# HVAC8-2.net
KiCad netlist of a schematic drawn in EAGLE
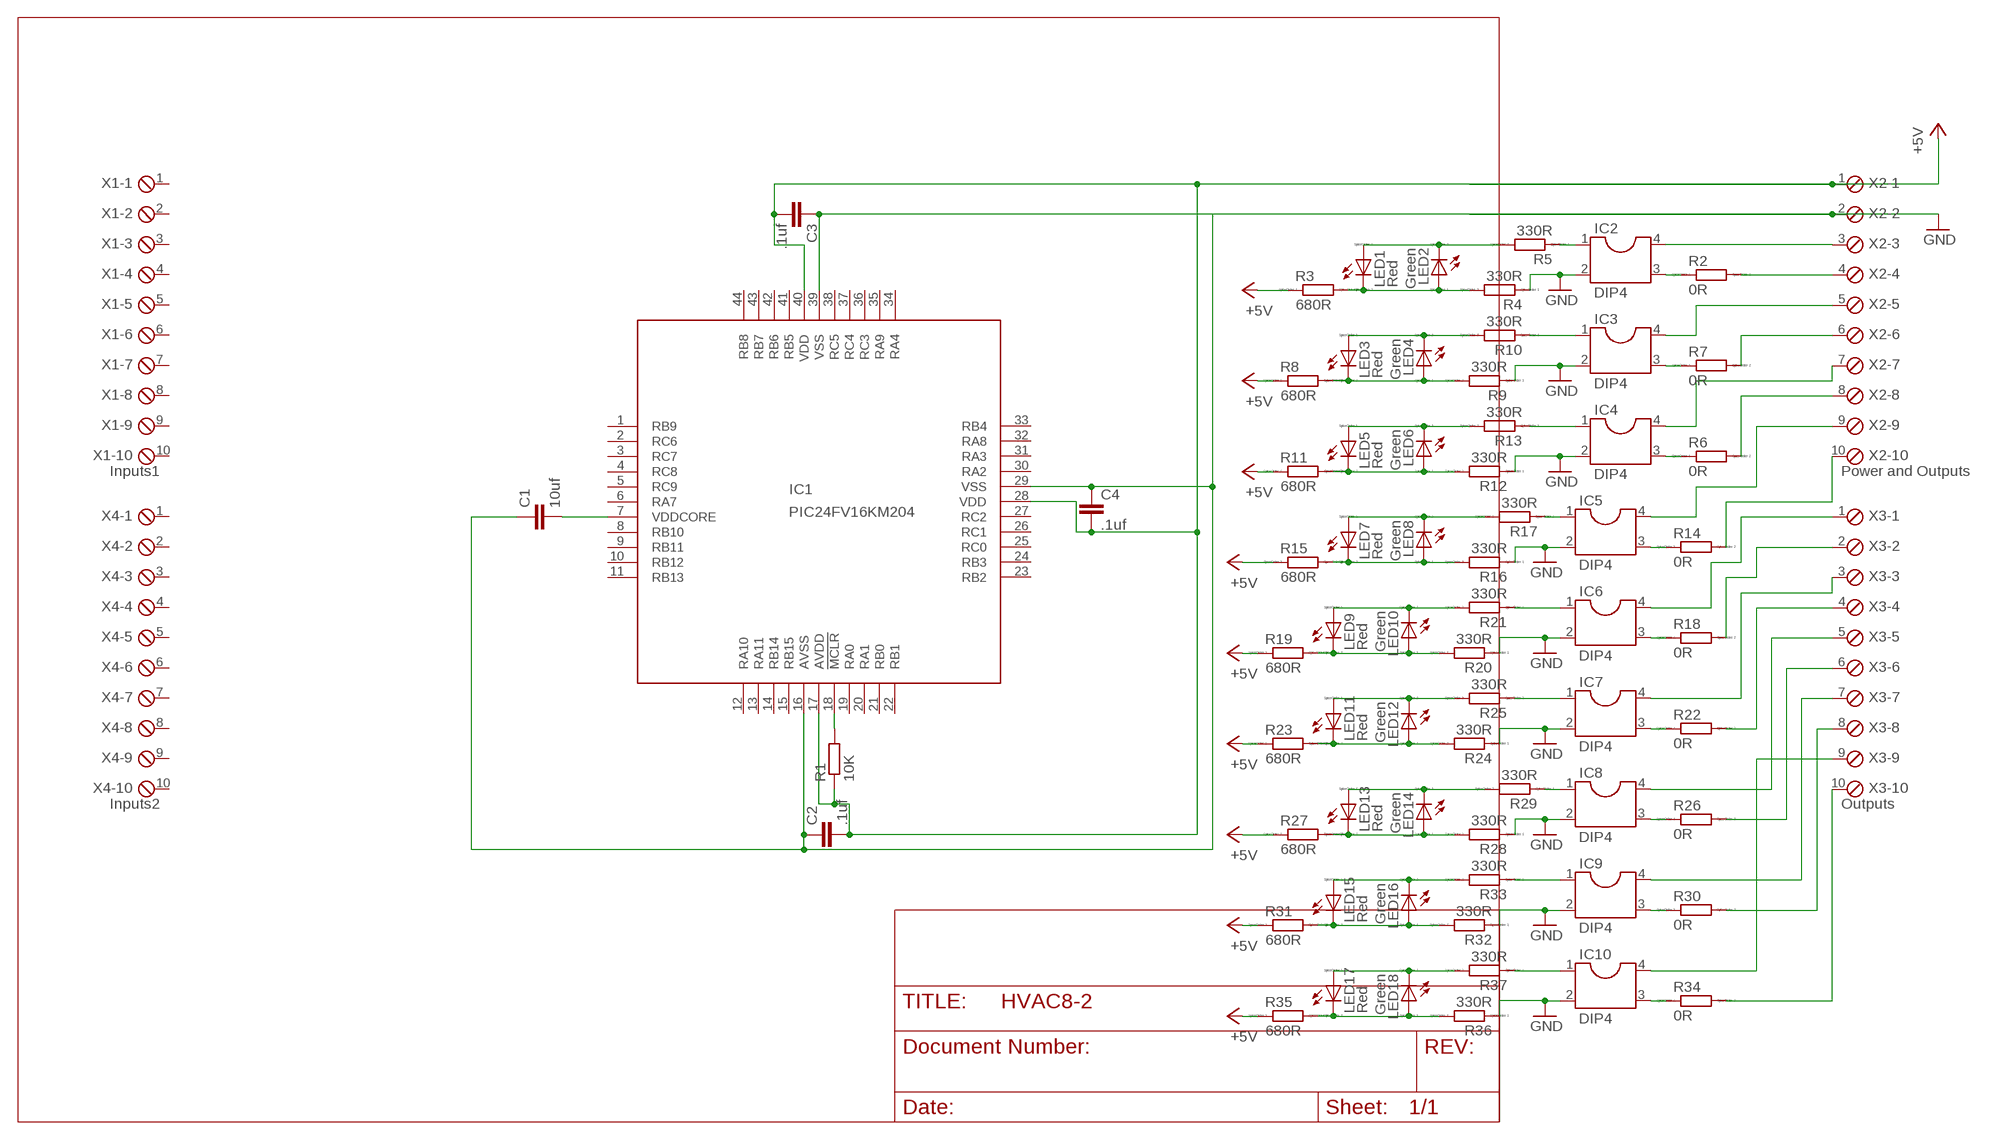
[diagram p0: schematic, sheet 1]

(export (version "E")
  (design (tool "Eeschema 10.0.6"))
  (components
    (comp (ref "C1")
      (value "10uf")
      (footprint "eagle-import:C1206")
      (libsource (lib "eagle-import") (part "C-EUC1206"))
    )
    (comp (ref "C2")
      (value ".1uf")
      (footprint "eagle-import:C1206")
      (libsource (lib "eagle-import") (part "C-EUC1206"))
    )
    (comp (ref "C3")
      (value ".1uf")
      (footprint "eagle-import:C1206")
      (libsource (lib "eagle-import") (part "C-EUC1206"))
    )
    (comp (ref "C4")
      (value ".1uf")
      (footprint "eagle-import:C1206")
      (libsource (lib "eagle-import") (part "C-EUC1206"))
    )
    (comp (ref "IC1")
      (value "PIC24FV16KM204")
      (footprint "eagle-import:TQFP44")
      (libsource (lib "eagle-import") (part "PIC24FV16KM204"))
    )
    (comp (ref "IC2")
      (value "DIP4")
      (footprint "eagle-import:SOCKET-04")
      (libsource (lib "eagle-import") (part "DIL4S"))
    )
    (comp (ref "IC3")
      (value "DIP4")
      (footprint "eagle-import:SOCKET-04")
      (libsource (lib "eagle-import") (part "DIL4S"))
    )
    (comp (ref "IC4")
      (value "DIP4")
      (footprint "eagle-import:SOCKET-04")
      (libsource (lib "eagle-import") (part "DIL4S"))
    )
    (comp (ref "IC5")
      (value "DIP4")
      (footprint "eagle-import:SOCKET-04")
      (libsource (lib "eagle-import") (part "DIL4S"))
    )
    (comp (ref "IC6")
      (value "DIP4")
      (footprint "eagle-import:SOCKET-04")
      (libsource (lib "eagle-import") (part "DIL4S"))
    )
    (comp (ref "IC7")
      (value "DIP4")
      (footprint "eagle-import:SOCKET-04")
      (libsource (lib "eagle-import") (part "DIL4S"))
    )
    (comp (ref "IC8")
      (value "DIP4")
      (footprint "eagle-import:SOCKET-04")
      (libsource (lib "eagle-import") (part "DIL4S"))
    )
    (comp (ref "IC9")
      (value "DIP4")
      (footprint "eagle-import:SOCKET-04")
      (libsource (lib "eagle-import") (part "DIL4S"))
    )
    (comp (ref "IC10")
      (value "DIP4")
      (footprint "eagle-import:SOCKET-04")
      (libsource (lib "eagle-import") (part "DIL4S"))
    )
    (comp (ref "LED1")
      (value "Red")
      (footprint "eagle-import:LED_1206")
      (libsource (lib "eagle-import") (part "LED_E"))
    )
    (comp (ref "LED2")
      (value "Green")
      (footprint "eagle-import:LED_1206")
      (libsource (lib "eagle-import") (part "LED_E"))
    )
    (comp (ref "LED3")
      (value "Red")
      (footprint "eagle-import:LED_1206")
      (libsource (lib "eagle-import") (part "LED_E"))
    )
    (comp (ref "LED4")
      (value "Green")
      (footprint "eagle-import:LED_1206")
      (libsource (lib "eagle-import") (part "LED_E"))
    )
    (comp (ref "LED5")
      (value "Red")
      (footprint "eagle-import:LED_1206")
      (libsource (lib "eagle-import") (part "LED_E"))
    )
    (comp (ref "LED6")
      (value "Green")
      (footprint "eagle-import:LED_1206")
      (libsource (lib "eagle-import") (part "LED_E"))
    )
    (comp (ref "LED7")
      (value "Red")
      (footprint "eagle-import:LED_1206")
      (libsource (lib "eagle-import") (part "LED_E"))
    )
    (comp (ref "LED8")
      (value "Green")
      (footprint "eagle-import:LED_1206")
      (libsource (lib "eagle-import") (part "LED_E"))
    )
    (comp (ref "LED9")
      (value "Red")
      (footprint "eagle-import:LED_1206")
      (libsource (lib "eagle-import") (part "LED_E"))
    )
    (comp (ref "LED10")
      (value "Green")
      (footprint "eagle-import:LED_1206")
      (libsource (lib "eagle-import") (part "LED_E"))
    )
    (comp (ref "LED11")
      (value "Red")
      (footprint "eagle-import:LED_1206")
      (libsource (lib "eagle-import") (part "LED_E"))
    )
    (comp (ref "LED12")
      (value "Green")
      (footprint "eagle-import:LED_1206")
      (libsource (lib "eagle-import") (part "LED_E"))
    )
    (comp (ref "LED13")
      (value "Red")
      (footprint "eagle-import:LED_1206")
      (libsource (lib "eagle-import") (part "LED_E"))
    )
    (comp (ref "LED14")
      (value "Green")
      (footprint "eagle-import:LED_1206")
      (libsource (lib "eagle-import") (part "LED_E"))
    )
    (comp (ref "LED15")
      (value "Red")
      (footprint "eagle-import:LED_1206")
      (libsource (lib "eagle-import") (part "LED_E"))
    )
    (comp (ref "LED16")
      (value "Green")
      (footprint "eagle-import:LED_1206")
      (libsource (lib "eagle-import") (part "LED_E"))
    )
    (comp (ref "LED17")
      (value "Red")
      (footprint "eagle-import:LED_1206")
      (libsource (lib "eagle-import") (part "LED_E"))
    )
    (comp (ref "LED18")
      (value "Green")
      (footprint "eagle-import:LED_1206")
      (libsource (lib "eagle-import") (part "LED_E"))
    )
    (comp (ref "R1")
      (value "10K")
      (footprint "eagle-import:R1206")
      (libsource (lib "eagle-import") (part "R-EU_R1206"))
    )
    (comp (ref "R2")
      (value "0R")
      (footprint "eagle-import:R1206")
      (libsource (lib "eagle-import") (part "RR1206"))
    )
    (comp (ref "R3")
      (value "680R")
      (footprint "eagle-import:R1206")
      (libsource (lib "eagle-import") (part "RR1206"))
    )
    (comp (ref "R4")
      (value "330R")
      (footprint "eagle-import:R1206")
      (libsource (lib "eagle-import") (part "RR1206"))
    )
    (comp (ref "R5")
      (value "330R")
      (footprint "eagle-import:R1206")
      (libsource (lib "eagle-import") (part "RR1206"))
    )
    (comp (ref "R6")
      (value "0R")
      (footprint "eagle-import:R1206")
      (libsource (lib "eagle-import") (part "RR1206"))
    )
    (comp (ref "R7")
      (value "0R")
      (footprint "eagle-import:R1206")
      (libsource (lib "eagle-import") (part "RR1206"))
    )
    (comp (ref "R8")
      (value "680R")
      (footprint "eagle-import:R1206")
      (libsource (lib "eagle-import") (part "RR1206"))
    )
    (comp (ref "R9")
      (value "330R")
      (footprint "eagle-import:R1206")
      (libsource (lib "eagle-import") (part "RR1206"))
    )
    (comp (ref "R10")
      (value "330R")
      (footprint "eagle-import:R1206")
      (libsource (lib "eagle-import") (part "RR1206"))
    )
    (comp (ref "R11")
      (value "680R")
      (footprint "eagle-import:R1206")
      (libsource (lib "eagle-import") (part "RR1206"))
    )
    (comp (ref "R12")
      (value "330R")
      (footprint "eagle-import:R1206")
      (libsource (lib "eagle-import") (part "RR1206"))
    )
    (comp (ref "R13")
      (value "330R")
      (footprint "eagle-import:R1206")
      (libsource (lib "eagle-import") (part "RR1206"))
    )
    (comp (ref "R14")
      (value "0R")
      (footprint "eagle-import:R1206")
      (libsource (lib "eagle-import") (part "RR1206"))
    )
    (comp (ref "R15")
      (value "680R")
      (footprint "eagle-import:R1206")
      (libsource (lib "eagle-import") (part "RR1206"))
    )
    (comp (ref "R16")
      (value "330R")
      (footprint "eagle-import:R1206")
      (libsource (lib "eagle-import") (part "RR1206"))
    )
    (comp (ref "R17")
      (value "330R")
      (footprint "eagle-import:R1206")
      (libsource (lib "eagle-import") (part "RR1206"))
    )
    (comp (ref "R18")
      (value "0R")
      (footprint "eagle-import:R1206")
      (libsource (lib "eagle-import") (part "RR1206"))
    )
    (comp (ref "R19")
      (value "680R")
      (footprint "eagle-import:R1206")
      (libsource (lib "eagle-import") (part "RR1206"))
    )
    (comp (ref "R20")
      (value "330R")
      (footprint "eagle-import:R1206")
      (libsource (lib "eagle-import") (part "RR1206"))
    )
    (comp (ref "R21")
      (value "330R")
      (footprint "eagle-import:R1206")
      (libsource (lib "eagle-import") (part "RR1206"))
    )
    (comp (ref "R22")
      (value "0R")
      (footprint "eagle-import:R1206")
      (libsource (lib "eagle-import") (part "RR1206"))
    )
    (comp (ref "R23")
      (value "680R")
      (footprint "eagle-import:R1206")
      (libsource (lib "eagle-import") (part "RR1206"))
    )
    (comp (ref "R24")
      (value "330R")
      (footprint "eagle-import:R1206")
      (libsource (lib "eagle-import") (part "RR1206"))
    )
    (comp (ref "R25")
      (value "330R")
      (footprint "eagle-import:R1206")
      (libsource (lib "eagle-import") (part "RR1206"))
    )
    (comp (ref "R26")
      (value "0R")
      (footprint "eagle-import:R1206")
      (libsource (lib "eagle-import") (part "RR1206"))
    )
    (comp (ref "R27")
      (value "680R")
      (footprint "eagle-import:R1206")
      (libsource (lib "eagle-import") (part "RR1206"))
    )
    (comp (ref "R28")
      (value "330R")
      (footprint "eagle-import:R1206")
      (libsource (lib "eagle-import") (part "RR1206"))
    )
    (comp (ref "R29")
      (value "330R")
      (footprint "eagle-import:R1206")
      (libsource (lib "eagle-import") (part "RR1206"))
    )
    (comp (ref "R30")
      (value "0R")
      (footprint "eagle-import:R1206")
      (libsource (lib "eagle-import") (part "RR1206"))
    )
    (comp (ref "R31")
      (value "680R")
      (footprint "eagle-import:R1206")
      (libsource (lib "eagle-import") (part "RR1206"))
    )
    (comp (ref "R32")
      (value "330R")
      (footprint "eagle-import:R1206")
      (libsource (lib "eagle-import") (part "RR1206"))
    )
    (comp (ref "R33")
      (value "330R")
      (footprint "eagle-import:R1206")
      (libsource (lib "eagle-import") (part "RR1206"))
    )
    (comp (ref "R34")
      (value "0R")
      (footprint "eagle-import:R1206")
      (libsource (lib "eagle-import") (part "RR1206"))
    )
    (comp (ref "R35")
      (value "680R")
      (footprint "eagle-import:R1206")
      (libsource (lib "eagle-import") (part "RR1206"))
    )
    (comp (ref "R36")
      (value "330R")
      (footprint "eagle-import:R1206")
      (libsource (lib "eagle-import") (part "RR1206"))
    )
    (comp (ref "R37")
      (value "330R")
      (footprint "eagle-import:R1206")
      (libsource (lib "eagle-import") (part "RR1206"))
    )
    (comp (ref "X1")
      (value "Inputs1")
      (footprint "eagle-import:10POL254")
      (libsource (lib "eagle-import") (part "MPT10"))
    )
    (comp (ref "X2")
      (value "Power and Outputs")
      (footprint "eagle-import:10POL254")
      (libsource (lib "eagle-import") (part "MPT10"))
    )
    (comp (ref "X3")
      (value "Outputs")
      (footprint "eagle-import:10POL254")
      (libsource (lib "eagle-import") (part "MPT10"))
    )
    (comp (ref "X4")
      (value "Inputs2")
      (footprint "eagle-import:10POL254")
      (libsource (lib "eagle-import") (part "MPT10"))
    )
  )
  (nets
    (net (code "1") (name "+5V") (class "Default")
      (node (ref "C2") (pin "2") (pinfunction "2_2") (pintype "passive"))
      (node (ref "C3") (pin "2") (pinfunction "2_2") (pintype "passive"))
      (node (ref "C4") (pin "2") (pinfunction "2_2") (pintype "passive"))
      (node (ref "IC1") (pin "17") (pinfunction "AVDD_17") (pintype "power_in"))
      (node (ref "IC1") (pin "28") (pinfunction "VDD_28") (pintype "power_in"))
      (node (ref "IC1") (pin "40") (pinfunction "VDD_40") (pintype "power_in"))
      (node (ref "R1") (pin "1") (pinfunction "1_1") (pintype "passive"))
      (node (ref "R11") (pin "1") (pinfunction "1_1") (pintype "passive"))
      (node (ref "R15") (pin "1") (pinfunction "1_1") (pintype "passive"))
      (node (ref "R19") (pin "1") (pinfunction "1_1") (pintype "passive"))
      (node (ref "R23") (pin "1") (pinfunction "1_1") (pintype "passive"))
      (node (ref "R27") (pin "1") (pinfunction "1_1") (pintype "passive"))
      (node (ref "R3") (pin "1") (pinfunction "1_1") (pintype "passive"))
      (node (ref "R31") (pin "1") (pinfunction "1_1") (pintype "passive"))
      (node (ref "R35") (pin "1") (pinfunction "1_1") (pintype "passive"))
      (node (ref "R8") (pin "1") (pinfunction "1_1") (pintype "passive"))
      (node (ref "X2") (pin "1") (pinfunction "1_1") (pintype "passive"))
    )
    (net (code "2") (name "GND") (class "Default")
      (node (ref "C1") (pin "1") (pinfunction "1_1") (pintype "passive"))
      (node (ref "C2") (pin "1") (pinfunction "1_1") (pintype "passive"))
      (node (ref "C3") (pin "1") (pinfunction "1_1") (pintype "passive"))
      (node (ref "C4") (pin "1") (pinfunction "1_1") (pintype "passive"))
      (node (ref "IC1") (pin "16") (pinfunction "AVSS_16") (pintype "power_in"))
      (node (ref "IC1") (pin "29") (pinfunction "VSS_29") (pintype "power_in"))
      (node (ref "IC1") (pin "39") (pinfunction "VSS_39") (pintype "power_in"))
      (node (ref "IC10") (pin "2") (pinfunction "2_2") (pintype "passive"))
      (node (ref "IC2") (pin "2") (pinfunction "2_2") (pintype "passive"))
      (node (ref "IC3") (pin "2") (pinfunction "2_2") (pintype "passive"))
      (node (ref "IC4") (pin "2") (pinfunction "2_2") (pintype "passive"))
      (node (ref "IC5") (pin "2") (pinfunction "2_2") (pintype "passive"))
      (node (ref "IC6") (pin "2") (pinfunction "2_2") (pintype "passive"))
      (node (ref "IC7") (pin "2") (pinfunction "2_2") (pintype "passive"))
      (node (ref "IC8") (pin "2") (pinfunction "2_2") (pintype "passive"))
      (node (ref "IC9") (pin "2") (pinfunction "2_2") (pintype "passive"))
      (node (ref "R12") (pin "1") (pinfunction "1_1") (pintype "passive"))
      (node (ref "R16") (pin "1") (pinfunction "1_1") (pintype "passive"))
      (node (ref "R20") (pin "1") (pinfunction "1_1") (pintype "passive"))
      (node (ref "R24") (pin "1") (pinfunction "1_1") (pintype "passive"))
      (node (ref "R28") (pin "1") (pinfunction "1_1") (pintype "passive"))
      (node (ref "R32") (pin "1") (pinfunction "1_1") (pintype "passive"))
      (node (ref "R36") (pin "1") (pinfunction "1_1") (pintype "passive"))
      (node (ref "R4") (pin "1") (pinfunction "1_1") (pintype "passive"))
      (node (ref "R9") (pin "1") (pinfunction "1_1") (pintype "passive"))
      (node (ref "X2") (pin "2") (pinfunction "1_2") (pintype "passive"))
    )
    (net (code "3") (name "Net-(IC1-VDDCORE)") (class "Default")
      (node (ref "C1") (pin "2") (pinfunction "2_2") (pintype "passive"))
      (node (ref "IC1") (pin "7") (pinfunction "VDDCORE_7") (pintype "power_in"))
    )
    (net (code "4") (name "Net-(IC1-~{MCLR})") (class "Default")
      (node (ref "IC1") (pin "18") (pinfunction "~{MCLR}_18") (pintype "bidirectional"))
      (node (ref "R1") (pin "2") (pinfunction "2_2") (pintype "passive"))
    )
    (net (code "5") (name "Net-(IC2-Pad1)") (class "Default")
      (node (ref "IC2") (pin "1") (pinfunction "1_1") (pintype "passive"))
      (node (ref "R5") (pin "1") (pinfunction "1_1") (pintype "passive"))
    )
    (net (code "6") (name "Net-(IC2-Pad3)") (class "Default")
      (node (ref "IC2") (pin "3") (pinfunction "3_3") (pintype "passive"))
      (node (ref "R2") (pin "1") (pinfunction "1_1") (pintype "passive"))
    )
    (net (code "7") (name "Net-(IC3-Pad1)") (class "Default")
      (node (ref "IC3") (pin "1") (pinfunction "1_1") (pintype "passive"))
      (node (ref "R10") (pin "1") (pinfunction "1_1") (pintype "passive"))
    )
    (net (code "8") (name "Net-(IC3-Pad3)") (class "Default")
      (node (ref "IC3") (pin "3") (pinfunction "3_3") (pintype "passive"))
      (node (ref "R7") (pin "1") (pinfunction "1_1") (pintype "passive"))
    )
    (net (code "9") (name "Net-(IC4-Pad1)") (class "Default")
      (node (ref "IC4") (pin "1") (pinfunction "1_1") (pintype "passive"))
      (node (ref "R13") (pin "1") (pinfunction "1_1") (pintype "passive"))
    )
    (net (code "10") (name "Net-(IC4-Pad3)") (class "Default")
      (node (ref "IC4") (pin "3") (pinfunction "3_3") (pintype "passive"))
      (node (ref "R6") (pin "1") (pinfunction "1_1") (pintype "passive"))
    )
    (net (code "11") (name "Net-(IC5-Pad1)") (class "Default")
      (node (ref "IC5") (pin "1") (pinfunction "1_1") (pintype "passive"))
      (node (ref "R17") (pin "1") (pinfunction "1_1") (pintype "passive"))
    )
    (net (code "12") (name "Net-(IC5-Pad3)") (class "Default")
      (node (ref "IC5") (pin "3") (pinfunction "3_3") (pintype "passive"))
      (node (ref "R14") (pin "1") (pinfunction "1_1") (pintype "passive"))
    )
    (net (code "13") (name "Net-(IC6-Pad1)") (class "Default")
      (node (ref "IC6") (pin "1") (pinfunction "1_1") (pintype "passive"))
      (node (ref "R21") (pin "1") (pinfunction "1_1") (pintype "passive"))
    )
    (net (code "14") (name "Net-(IC6-Pad3)") (class "Default")
      (node (ref "IC6") (pin "3") (pinfunction "3_3") (pintype "passive"))
      (node (ref "R18") (pin "1") (pinfunction "1_1") (pintype "passive"))
    )
    (net (code "15") (name "Net-(IC6-Pad4)") (class "Default")
      (node (ref "IC6") (pin "4") (pinfunction "4_4") (pintype "passive"))
      (node (ref "X3") (pin "1") (pinfunction "1_1") (pintype "passive"))
    )
    (net (code "16") (name "Net-(IC7-Pad1)") (class "Default")
      (node (ref "IC7") (pin "1") (pinfunction "1_1") (pintype "passive"))
      (node (ref "R25") (pin "1") (pinfunction "1_1") (pintype "passive"))
    )
    (net (code "17") (name "Net-(IC7-Pad3)") (class "Default")
      (node (ref "IC7") (pin "3") (pinfunction "3_3") (pintype "passive"))
      (node (ref "R22") (pin "1") (pinfunction "1_1") (pintype "passive"))
    )
    (net (code "18") (name "Net-(IC8-Pad1)") (class "Default")
      (node (ref "IC8") (pin "1") (pinfunction "1_1") (pintype "passive"))
      (node (ref "R29") (pin "1") (pinfunction "1_1") (pintype "passive"))
    )
    (net (code "19") (name "Net-(IC8-Pad3)") (class "Default")
      (node (ref "IC8") (pin "3") (pinfunction "3_3") (pintype "passive"))
      (node (ref "R26") (pin "1") (pinfunction "1_1") (pintype "passive"))
    )
    (net (code "20") (name "Net-(IC9-Pad1)") (class "Default")
      (node (ref "IC9") (pin "1") (pinfunction "1_1") (pintype "passive"))
      (node (ref "R33") (pin "1") (pinfunction "1_1") (pintype "passive"))
    )
    (net (code "21") (name "Net-(IC9-Pad3)") (class "Default")
      (node (ref "IC9") (pin "3") (pinfunction "3_3") (pintype "passive"))
      (node (ref "R30") (pin "1") (pinfunction "1_1") (pintype "passive"))
    )
    (net (code "22") (name "Net-(IC10-Pad1)") (class "Default")
      (node (ref "IC10") (pin "1") (pinfunction "1_1") (pintype "passive"))
      (node (ref "R37") (pin "1") (pinfunction "1_1") (pintype "passive"))
    )
    (net (code "23") (name "Net-(IC10-Pad3)") (class "Default")
      (node (ref "IC10") (pin "3") (pinfunction "3_3") (pintype "passive"))
      (node (ref "R34") (pin "1") (pinfunction "1_1") (pintype "passive"))
    )
    (net (code "24") (name "Net-(LED1-PadA)") (class "Default")
      (node (ref "LED1") (pin "A") (pinfunction "A_A") (pintype "passive"))
      (node (ref "LED2") (pin "C") (pinfunction "C_C") (pintype "passive"))
      (node (ref "R5") (pin "2") (pinfunction "2_2") (pintype "passive"))
    )
    (net (code "25") (name "Net-(LED1-PadC)") (class "Default")
      (node (ref "LED1") (pin "C") (pinfunction "C_C") (pintype "passive"))
      (node (ref "LED2") (pin "A") (pinfunction "A_A") (pintype "passive"))
      (node (ref "R3") (pin "2") (pinfunction "2_2") (pintype "passive"))
      (node (ref "R4") (pin "2") (pinfunction "2_2") (pintype "passive"))
    )
    (net (code "26") (name "Net-(LED3-PadA)") (class "Default")
      (node (ref "LED3") (pin "A") (pinfunction "A_A") (pintype "passive"))
      (node (ref "LED4") (pin "C") (pinfunction "C_C") (pintype "passive"))
      (node (ref "R10") (pin "2") (pinfunction "2_2") (pintype "passive"))
    )
    (net (code "27") (name "Net-(LED3-PadC)") (class "Default")
      (node (ref "LED3") (pin "C") (pinfunction "C_C") (pintype "passive"))
      (node (ref "LED4") (pin "A") (pinfunction "A_A") (pintype "passive"))
      (node (ref "R8") (pin "2") (pinfunction "2_2") (pintype "passive"))
      (node (ref "R9") (pin "2") (pinfunction "2_2") (pintype "passive"))
    )
    (net (code "28") (name "Net-(LED5-PadA)") (class "Default")
      (node (ref "LED5") (pin "A") (pinfunction "A_A") (pintype "passive"))
      (node (ref "LED6") (pin "C") (pinfunction "C_C") (pintype "passive"))
      (node (ref "R13") (pin "2") (pinfunction "2_2") (pintype "passive"))
    )
    (net (code "29") (name "Net-(LED5-PadC)") (class "Default")
      (node (ref "LED5") (pin "C") (pinfunction "C_C") (pintype "passive"))
      (node (ref "LED6") (pin "A") (pinfunction "A_A") (pintype "passive"))
      (node (ref "R11") (pin "2") (pinfunction "2_2") (pintype "passive"))
      (node (ref "R12") (pin "2") (pinfunction "2_2") (pintype "passive"))
    )
    (net (code "30") (name "Net-(LED7-PadA)") (class "Default")
      (node (ref "LED7") (pin "A") (pinfunction "A_A") (pintype "passive"))
      (node (ref "LED8") (pin "C") (pinfunction "C_C") (pintype "passive"))
      (node (ref "R17") (pin "2") (pinfunction "2_2") (pintype "passive"))
    )
    (net (code "31") (name "Net-(LED7-PadC)") (class "Default")
      (node (ref "LED7") (pin "C") (pinfunction "C_C") (pintype "passive"))
      (node (ref "LED8") (pin "A") (pinfunction "A_A") (pintype "passive"))
      (node (ref "R15") (pin "2") (pinfunction "2_2") (pintype "passive"))
      (node (ref "R16") (pin "2") (pinfunction "2_2") (pintype "passive"))
    )
    (net (code "32") (name "Net-(LED10-PadA)") (class "Default")
      (node (ref "LED10") (pin "A") (pinfunction "A_A") (pintype "passive"))
      (node (ref "LED9") (pin "C") (pinfunction "C_C") (pintype "passive"))
      (node (ref "R19") (pin "2") (pinfunction "2_2") (pintype "passive"))
      (node (ref "R20") (pin "2") (pinfunction "2_2") (pintype "passive"))
    )
    (net (code "33") (name "Net-(LED10-PadC)") (class "Default")
      (node (ref "LED10") (pin "C") (pinfunction "C_C") (pintype "passive"))
      (node (ref "LED9") (pin "A") (pinfunction "A_A") (pintype "passive"))
      (node (ref "R21") (pin "2") (pinfunction "2_2") (pintype "passive"))
    )
    (net (code "34") (name "Net-(LED11-PadA)") (class "Default")
      (node (ref "LED11") (pin "A") (pinfunction "A_A") (pintype "passive"))
      (node (ref "LED12") (pin "C") (pinfunction "C_C") (pintype "passive"))
      (node (ref "R25") (pin "2") (pinfunction "2_2") (pintype "passive"))
    )
    (net (code "35") (name "Net-(LED11-PadC)") (class "Default")
      (node (ref "LED11") (pin "C") (pinfunction "C_C") (pintype "passive"))
      (node (ref "LED12") (pin "A") (pinfunction "A_A") (pintype "passive"))
      (node (ref "R23") (pin "2") (pinfunction "2_2") (pintype "passive"))
      (node (ref "R24") (pin "2") (pinfunction "2_2") (pintype "passive"))
    )
    (net (code "36") (name "Net-(LED13-PadA)") (class "Default")
      (node (ref "LED13") (pin "A") (pinfunction "A_A") (pintype "passive"))
      (node (ref "LED14") (pin "C") (pinfunction "C_C") (pintype "passive"))
      (node (ref "R29") (pin "2") (pinfunction "2_2") (pintype "passive"))
    )
    (net (code "37") (name "Net-(LED13-PadC)") (class "Default")
      (node (ref "LED13") (pin "C") (pinfunction "C_C") (pintype "passive"))
      (node (ref "LED14") (pin "A") (pinfunction "A_A") (pintype "passive"))
      (node (ref "R27") (pin "2") (pinfunction "2_2") (pintype "passive"))
      (node (ref "R28") (pin "2") (pinfunction "2_2") (pintype "passive"))
    )
    (net (code "38") (name "Net-(LED15-PadA)") (class "Default")
      (node (ref "LED15") (pin "A") (pinfunction "A_A") (pintype "passive"))
      (node (ref "LED16") (pin "C") (pinfunction "C_C") (pintype "passive"))
      (node (ref "R33") (pin "2") (pinfunction "2_2") (pintype "passive"))
    )
    (net (code "39") (name "Net-(LED15-PadC)") (class "Default")
      (node (ref "LED15") (pin "C") (pinfunction "C_C") (pintype "passive"))
      (node (ref "LED16") (pin "A") (pinfunction "A_A") (pintype "passive"))
      (node (ref "R31") (pin "2") (pinfunction "2_2") (pintype "passive"))
      (node (ref "R32") (pin "2") (pinfunction "2_2") (pintype "passive"))
    )
    (net (code "40") (name "Net-(LED17-PadA)") (class "Default")
      (node (ref "LED17") (pin "A") (pinfunction "A_A") (pintype "passive"))
      (node (ref "LED18") (pin "C") (pinfunction "C_C") (pintype "passive"))
      (node (ref "R37") (pin "2") (pinfunction "2_2") (pintype "passive"))
    )
    (net (code "41") (name "Net-(LED17-PadC)") (class "Default")
      (node (ref "LED17") (pin "C") (pinfunction "C_C") (pintype "passive"))
      (node (ref "LED18") (pin "A") (pinfunction "A_A") (pintype "passive"))
      (node (ref "R35") (pin "2") (pinfunction "2_2") (pintype "passive"))
      (node (ref "R36") (pin "2") (pinfunction "2_2") (pintype "passive"))
    )
    (net (code "42") (name "Net-(X2B-1)") (class "Default")
      (node (ref "R14") (pin "2") (pinfunction "2_2") (pintype "passive"))
      (node (ref "X2") (pin "10") (pinfunction "1_10") (pintype "passive"))
    )
    (net (code "43") (name "Net-(X2D-1)") (class "Default")
      (node (ref "IC2") (pin "4") (pinfunction "4_4") (pintype "passive"))
      (node (ref "X2") (pin "3") (pinfunction "1_3") (pintype "passive"))
    )
    (net (code "44") (name "Net-(X2E-1)") (class "Default")
      (node (ref "R2") (pin "2") (pinfunction "2_2") (pintype "passive"))
      (node (ref "X2") (pin "4") (pinfunction "1_4") (pintype "passive"))
    )
    (net (code "45") (name "Net-(X2F-1)") (class "Default")
      (node (ref "IC3") (pin "4") (pinfunction "4_4") (pintype "passive"))
      (node (ref "X2") (pin "5") (pinfunction "1_5") (pintype "passive"))
    )
    (net (code "46") (name "Net-(X2G-1)") (class "Default")
      (node (ref "R7") (pin "2") (pinfunction "2_2") (pintype "passive"))
      (node (ref "X2") (pin "6") (pinfunction "1_6") (pintype "passive"))
    )
    (net (code "47") (name "Net-(X2H-1)") (class "Default")
      (node (ref "IC4") (pin "4") (pinfunction "4_4") (pintype "passive"))
      (node (ref "X2") (pin "7") (pinfunction "1_7") (pintype "passive"))
    )
    (net (code "48") (name "Net-(X2I-1)") (class "Default")
      (node (ref "R6") (pin "2") (pinfunction "2_2") (pintype "passive"))
      (node (ref "X2") (pin "8") (pinfunction "1_8") (pintype "passive"))
    )
    (net (code "49") (name "Net-(X2J-1)") (class "Default")
      (node (ref "IC5") (pin "4") (pinfunction "4_4") (pintype "passive"))
      (node (ref "X2") (pin "9") (pinfunction "1_9") (pintype "passive"))
    )
    (net (code "50") (name "Net-(X3B-1)") (class "Default")
      (node (ref "R34") (pin "2") (pinfunction "2_2") (pintype "passive"))
      (node (ref "X3") (pin "10") (pinfunction "1_10") (pintype "passive"))
    )
    (net (code "51") (name "Net-(X3C-1)") (class "Default")
      (node (ref "R18") (pin "2") (pinfunction "2_2") (pintype "passive"))
      (node (ref "X3") (pin "2") (pinfunction "1_2") (pintype "passive"))
    )
    (net (code "52") (name "Net-(X3D-1)") (class "Default")
      (node (ref "IC7") (pin "4") (pinfunction "4_4") (pintype "passive"))
      (node (ref "X3") (pin "3") (pinfunction "1_3") (pintype "passive"))
    )
    (net (code "53") (name "Net-(X3E-1)") (class "Default")
      (node (ref "R22") (pin "2") (pinfunction "2_2") (pintype "passive"))
      (node (ref "X3") (pin "4") (pinfunction "1_4") (pintype "passive"))
    )
    (net (code "54") (name "Net-(X3F-1)") (class "Default")
      (node (ref "IC8") (pin "4") (pinfunction "4_4") (pintype "passive"))
      (node (ref "X3") (pin "5") (pinfunction "1_5") (pintype "passive"))
    )
    (net (code "55") (name "Net-(X3G-1)") (class "Default")
      (node (ref "R26") (pin "2") (pinfunction "2_2") (pintype "passive"))
      (node (ref "X3") (pin "6") (pinfunction "1_6") (pintype "passive"))
    )
    (net (code "56") (name "Net-(X3H-1)") (class "Default")
      (node (ref "IC9") (pin "4") (pinfunction "4_4") (pintype "passive"))
      (node (ref "X3") (pin "7") (pinfunction "1_7") (pintype "passive"))
    )
    (net (code "57") (name "Net-(X3I-1)") (class "Default")
      (node (ref "R30") (pin "2") (pinfunction "2_2") (pintype "passive"))
      (node (ref "X3") (pin "8") (pinfunction "1_8") (pintype "passive"))
    )
    (net (code "58") (name "Net-(X3J-1)") (class "Default")
      (node (ref "IC10") (pin "4") (pinfunction "4_4") (pintype "passive"))
      (node (ref "X3") (pin "9") (pinfunction "1_9") (pintype "passive"))
    )
    (net (code "59") (name "unconnected-(IC1-RA0-Pad19)") (class "Default")
      (node (ref "IC1") (pin "19") (pinfunction "RA0_19") (pintype "bidirectional"))
    )
    (net (code "60") (name "unconnected-(IC1-RA1-Pad20)") (class "Default")
      (node (ref "IC1") (pin "20") (pinfunction "RA1_20") (pintype "bidirectional"))
    )
    (net (code "61") (name "unconnected-(IC1-RA2-Pad30)") (class "Default")
      (node (ref "IC1") (pin "30") (pinfunction "RA2_30") (pintype "bidirectional"))
    )
    (net (code "62") (name "unconnected-(IC1-RA3-Pad31)") (class "Default")
      (node (ref "IC1") (pin "31") (pinfunction "RA3_31") (pintype "bidirectional"))
    )
    (net (code "63") (name "unconnected-(IC1-RA4-Pad34)") (class "Default")
      (node (ref "IC1") (pin "34") (pinfunction "RA4_34") (pintype "bidirectional"))
    )
    (net (code "64") (name "unconnected-(IC1-RA7-Pad6)") (class "Default")
      (node (ref "IC1") (pin "6") (pinfunction "RA7_6") (pintype "bidirectional"))
    )
    (net (code "65") (name "unconnected-(IC1-RA8-Pad32)") (class "Default")
      (node (ref "IC1") (pin "32") (pinfunction "RA8_32") (pintype "bidirectional"))
    )
    (net (code "66") (name "unconnected-(IC1-RA9-Pad35)") (class "Default")
      (node (ref "IC1") (pin "35") (pinfunction "RA9_35") (pintype "bidirectional"))
    )
    (net (code "67") (name "unconnected-(IC1-RA10-Pad12)") (class "Default")
      (node (ref "IC1") (pin "12") (pinfunction "RA10_12") (pintype "bidirectional"))
    )
    (net (code "68") (name "unconnected-(IC1-RA11-Pad13)") (class "Default")
      (node (ref "IC1") (pin "13") (pinfunction "RA11_13") (pintype "bidirectional"))
    )
    (net (code "69") (name "unconnected-(IC1-RB0-Pad21)") (class "Default")
      (node (ref "IC1") (pin "21") (pinfunction "RB0_21") (pintype "bidirectional"))
    )
    (net (code "70") (name "unconnected-(IC1-RB1-Pad22)") (class "Default")
      (node (ref "IC1") (pin "22") (pinfunction "RB1_22") (pintype "bidirectional"))
    )
    (net (code "71") (name "unconnected-(IC1-RB2-Pad23)") (class "Default")
      (node (ref "IC1") (pin "23") (pinfunction "RB2_23") (pintype "bidirectional"))
    )
    (net (code "72") (name "unconnected-(IC1-RB3-Pad24)") (class "Default")
      (node (ref "IC1") (pin "24") (pinfunction "RB3_24") (pintype "bidirectional"))
    )
    (net (code "73") (name "unconnected-(IC1-RB4-Pad33)") (class "Default")
      (node (ref "IC1") (pin "33") (pinfunction "RB4_33") (pintype "bidirectional"))
    )
    (net (code "74") (name "unconnected-(IC1-RB5-Pad41)") (class "Default")
      (node (ref "IC1") (pin "41") (pinfunction "RB5_41") (pintype "bidirectional"))
    )
    (net (code "75") (name "unconnected-(IC1-RB6-Pad42)") (class "Default")
      (node (ref "IC1") (pin "42") (pinfunction "RB6_42") (pintype "bidirectional"))
    )
    (net (code "76") (name "unconnected-(IC1-RB7-Pad43)") (class "Default")
      (node (ref "IC1") (pin "43") (pinfunction "RB7_43") (pintype "bidirectional"))
    )
    (net (code "77") (name "unconnected-(IC1-RB8-Pad44)") (class "Default")
      (node (ref "IC1") (pin "44") (pinfunction "RB8_44") (pintype "bidirectional"))
    )
    (net (code "78") (name "unconnected-(IC1-RB9-Pad1)") (class "Default")
      (node (ref "IC1") (pin "1") (pinfunction "RB9_1") (pintype "bidirectional"))
    )
    (net (code "79") (name "unconnected-(IC1-RB10-Pad8)") (class "Default")
      (node (ref "IC1") (pin "8") (pinfunction "RB10_8") (pintype "bidirectional"))
    )
    (net (code "80") (name "unconnected-(IC1-RB11-Pad9)") (class "Default")
      (node (ref "IC1") (pin "9") (pinfunction "RB11_9") (pintype "bidirectional"))
    )
    (net (code "81") (name "unconnected-(IC1-RB12-Pad10)") (class "Default")
      (node (ref "IC1") (pin "10") (pinfunction "RB12_10") (pintype "bidirectional"))
    )
    (net (code "82") (name "unconnected-(IC1-RB13-Pad11)") (class "Default")
      (node (ref "IC1") (pin "11") (pinfunction "RB13_11") (pintype "bidirectional"))
    )
    (net (code "83") (name "unconnected-(IC1-RB14-Pad14)") (class "Default")
      (node (ref "IC1") (pin "14") (pinfunction "RB14_14") (pintype "bidirectional"))
    )
    (net (code "84") (name "unconnected-(IC1-RB15-Pad15)") (class "Default")
      (node (ref "IC1") (pin "15") (pinfunction "RB15_15") (pintype "bidirectional"))
    )
    (net (code "85") (name "unconnected-(IC1-RC0-Pad25)") (class "Default")
      (node (ref "IC1") (pin "25") (pinfunction "RC0_25") (pintype "bidirectional"))
    )
    (net (code "86") (name "unconnected-(IC1-RC1-Pad26)") (class "Default")
      (node (ref "IC1") (pin "26") (pinfunction "RC1_26") (pintype "bidirectional"))
    )
    (net (code "87") (name "unconnected-(IC1-RC2-Pad27)") (class "Default")
      (node (ref "IC1") (pin "27") (pinfunction "RC2_27") (pintype "bidirectional"))
    )
    (net (code "88") (name "unconnected-(IC1-RC3-Pad36)") (class "Default")
      (node (ref "IC1") (pin "36") (pinfunction "RC3_36") (pintype "bidirectional"))
    )
    (net (code "89") (name "unconnected-(IC1-RC4-Pad37)") (class "Default")
      (node (ref "IC1") (pin "37") (pinfunction "RC4_37") (pintype "bidirectional"))
    )
    (net (code "90") (name "unconnected-(IC1-RC5-Pad38)") (class "Default")
      (node (ref "IC1") (pin "38") (pinfunction "RC5_38") (pintype "bidirectional"))
    )
    (net (code "91") (name "unconnected-(IC1-RC6-Pad2)") (class "Default")
      (node (ref "IC1") (pin "2") (pinfunction "RC6_2") (pintype "bidirectional"))
    )
    (net (code "92") (name "unconnected-(IC1-RC7-Pad3)") (class "Default")
      (node (ref "IC1") (pin "3") (pinfunction "RC7_3") (pintype "bidirectional"))
    )
    (net (code "93") (name "unconnected-(IC1-RC8-Pad4)") (class "Default")
      (node (ref "IC1") (pin "4") (pinfunction "RC8_4") (pintype "bidirectional"))
    )
    (net (code "94") (name "unconnected-(IC1-RC9-Pad5)") (class "Default")
      (node (ref "IC1") (pin "5") (pinfunction "RC9_5") (pintype "bidirectional"))
    )
    (net (code "95") (name "unconnected-(X1-Pad1)") (class "Default")
      (node (ref "X1") (pin "1") (pinfunction "1_1") (pintype "passive"))
    )
    (net (code "96") (name "unconnected-(X1B-1-Pad10)") (class "Default")
      (node (ref "X1") (pin "10") (pinfunction "1_10") (pintype "passive"))
    )
    (net (code "97") (name "unconnected-(X1C-1-Pad2)") (class "Default")
      (node (ref "X1") (pin "2") (pinfunction "1_2") (pintype "passive"))
    )
    (net (code "98") (name "unconnected-(X1D-1-Pad3)") (class "Default")
      (node (ref "X1") (pin "3") (pinfunction "1_3") (pintype "passive"))
    )
    (net (code "99") (name "unconnected-(X1E-1-Pad4)") (class "Default")
      (node (ref "X1") (pin "4") (pinfunction "1_4") (pintype "passive"))
    )
    (net (code "100") (name "unconnected-(X1F-1-Pad5)") (class "Default")
      (node (ref "X1") (pin "5") (pinfunction "1_5") (pintype "passive"))
    )
    (net (code "101") (name "unconnected-(X1G-1-Pad6)") (class "Default")
      (node (ref "X1") (pin "6") (pinfunction "1_6") (pintype "passive"))
    )
    (net (code "102") (name "unconnected-(X1H-1-Pad7)") (class "Default")
      (node (ref "X1") (pin "7") (pinfunction "1_7") (pintype "passive"))
    )
    (net (code "103") (name "unconnected-(X1I-1-Pad8)") (class "Default")
      (node (ref "X1") (pin "8") (pinfunction "1_8") (pintype "passive"))
    )
    (net (code "104") (name "unconnected-(X1J-1-Pad9)") (class "Default")
      (node (ref "X1") (pin "9") (pinfunction "1_9") (pintype "passive"))
    )
    (net (code "105") (name "unconnected-(X4-Pad1)") (class "Default")
      (node (ref "X4") (pin "1") (pinfunction "1_1") (pintype "passive"))
    )
    (net (code "106") (name "unconnected-(X4B-1-Pad10)") (class "Default")
      (node (ref "X4") (pin "10") (pinfunction "1_10") (pintype "passive"))
    )
    (net (code "107") (name "unconnected-(X4C-1-Pad2)") (class "Default")
      (node (ref "X4") (pin "2") (pinfunction "1_2") (pintype "passive"))
    )
    (net (code "108") (name "unconnected-(X4D-1-Pad3)") (class "Default")
      (node (ref "X4") (pin "3") (pinfunction "1_3") (pintype "passive"))
    )
    (net (code "109") (name "unconnected-(X4E-1-Pad4)") (class "Default")
      (node (ref "X4") (pin "4") (pinfunction "1_4") (pintype "passive"))
    )
    (net (code "110") (name "unconnected-(X4F-1-Pad5)") (class "Default")
      (node (ref "X4") (pin "5") (pinfunction "1_5") (pintype "passive"))
    )
    (net (code "111") (name "unconnected-(X4G-1-Pad6)") (class "Default")
      (node (ref "X4") (pin "6") (pinfunction "1_6") (pintype "passive"))
    )
    (net (code "112") (name "unconnected-(X4H-1-Pad7)") (class "Default")
      (node (ref "X4") (pin "7") (pinfunction "1_7") (pintype "passive"))
    )
    (net (code "113") (name "unconnected-(X4I-1-Pad8)") (class "Default")
      (node (ref "X4") (pin "8") (pinfunction "1_8") (pintype "passive"))
    )
    (net (code "114") (name "unconnected-(X4J-1-Pad9)") (class "Default")
      (node (ref "X4") (pin "9") (pinfunction "1_9") (pintype "passive"))
    )
  )
)
